# CP_State_LEDs.net
KiCad netlist of a schematic drawn in EAGLE
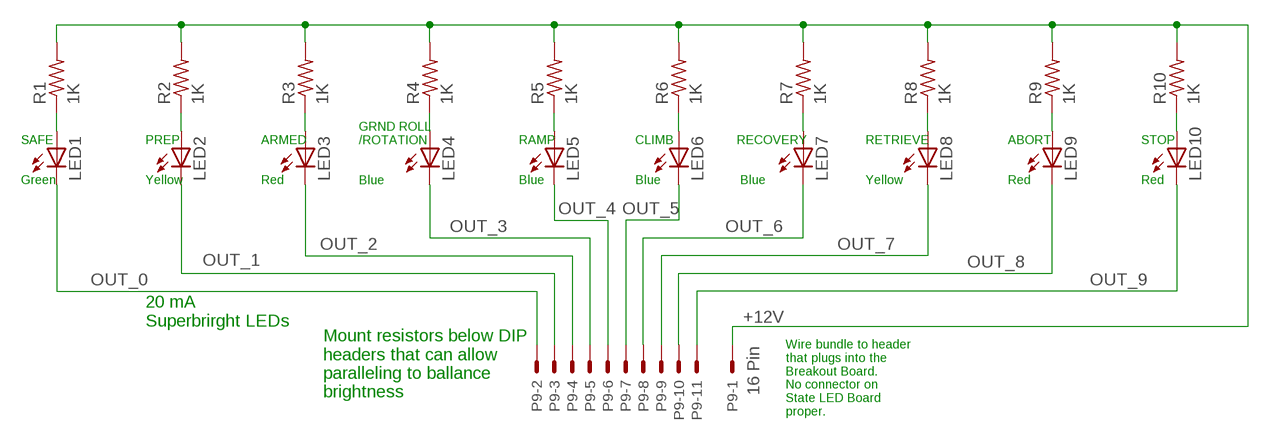
[diagram p0: schematic, sheet 1]

(export (version "E")
  (design (tool "Eeschema 10.0.6"))
  (components
    (comp (ref "LED1")
      (value "LED5MM")
      (footprint "eagle-import:LED5MM")
      (libsource (lib "eagle-import") (part "LED5MM"))
    )
    (comp (ref "LED2")
      (value "LED5MM")
      (footprint "eagle-import:LED5MM")
      (libsource (lib "eagle-import") (part "LED5MM"))
    )
    (comp (ref "LED3")
      (value "LED5MM")
      (footprint "eagle-import:LED5MM")
      (libsource (lib "eagle-import") (part "LED5MM"))
    )
    (comp (ref "LED4")
      (value "LED5MM")
      (footprint "eagle-import:LED5MM")
      (libsource (lib "eagle-import") (part "LED5MM"))
    )
    (comp (ref "LED5")
      (value "LED5MM")
      (footprint "eagle-import:LED5MM")
      (libsource (lib "eagle-import") (part "LED5MM"))
    )
    (comp (ref "LED6")
      (value "LED5MM")
      (footprint "eagle-import:LED5MM")
      (libsource (lib "eagle-import") (part "LED5MM"))
    )
    (comp (ref "LED7")
      (value "LED5MM")
      (footprint "eagle-import:LED5MM")
      (libsource (lib "eagle-import") (part "LED5MM"))
    )
    (comp (ref "LED8")
      (value "LED5MM")
      (footprint "eagle-import:LED5MM")
      (libsource (lib "eagle-import") (part "LED5MM"))
    )
    (comp (ref "LED9")
      (value "LED5MM")
      (footprint "eagle-import:LED5MM")
      (libsource (lib "eagle-import") (part "LED5MM"))
    )
    (comp (ref "LED10")
      (value "LED5MM")
      (footprint "eagle-import:LED5MM")
      (libsource (lib "eagle-import") (part "LED5MM"))
    )
    (comp (ref "P9")
      (value "16 Pin")
      (footprint "eagle-import:70543-20")
      (libsource (lib "eagle-import") (part "C-GRID-20-70543"))
    )
    (comp (ref "R1")
      (value "1K")
      (footprint "eagle-import:V234_12")
      (libsource (lib "eagle-import") (part "R-US_V234/12"))
    )
    (comp (ref "R2")
      (value "1K")
      (footprint "eagle-import:V234_12")
      (libsource (lib "eagle-import") (part "R-US_V234/12"))
    )
    (comp (ref "R3")
      (value "1K")
      (footprint "eagle-import:V234_12")
      (libsource (lib "eagle-import") (part "R-US_V234/12"))
    )
    (comp (ref "R4")
      (value "1K")
      (footprint "eagle-import:V234_12")
      (libsource (lib "eagle-import") (part "R-US_V234/12"))
    )
    (comp (ref "R5")
      (value "1K")
      (footprint "eagle-import:V234_12")
      (libsource (lib "eagle-import") (part "R-US_V234/12"))
    )
    (comp (ref "R6")
      (value "1K")
      (footprint "eagle-import:V234_12")
      (libsource (lib "eagle-import") (part "R-US_V234/12"))
    )
    (comp (ref "R7")
      (value "1K")
      (footprint "eagle-import:V234_12")
      (libsource (lib "eagle-import") (part "R-US_V234/12"))
    )
    (comp (ref "R8")
      (value "1K")
      (footprint "eagle-import:V234_12")
      (libsource (lib "eagle-import") (part "R-US_V234/12"))
    )
    (comp (ref "R9")
      (value "1K")
      (footprint "eagle-import:V234_12")
      (libsource (lib "eagle-import") (part "R-US_V234/12"))
    )
    (comp (ref "R10")
      (value "1K")
      (footprint "eagle-import:V234_12")
      (libsource (lib "eagle-import") (part "R-US_V234/12"))
    )
  )
  (nets
    (net (code "1") (name "/+12V") (class "Default")
      (node (ref "P9") (pin "1") (pinfunction "S_1") (pintype "passive"))
      (node (ref "R1") (pin "2") (pinfunction "2_2") (pintype "passive"))
      (node (ref "R10") (pin "2") (pinfunction "2_2") (pintype "passive"))
      (node (ref "R2") (pin "2") (pinfunction "2_2") (pintype "passive"))
      (node (ref "R3") (pin "2") (pinfunction "2_2") (pintype "passive"))
      (node (ref "R4") (pin "2") (pinfunction "2_2") (pintype "passive"))
      (node (ref "R5") (pin "2") (pinfunction "2_2") (pintype "passive"))
      (node (ref "R6") (pin "2") (pinfunction "2_2") (pintype "passive"))
      (node (ref "R7") (pin "2") (pinfunction "2_2") (pintype "passive"))
      (node (ref "R8") (pin "2") (pinfunction "2_2") (pintype "passive"))
      (node (ref "R9") (pin "2") (pinfunction "2_2") (pintype "passive"))
    )
    (net (code "2") (name "/OUT_0") (class "Default")
      (node (ref "LED1") (pin "K") (pinfunction "C_K") (pintype "passive"))
      (node (ref "P9") (pin "2") (pinfunction "S_2") (pintype "passive"))
    )
    (net (code "3") (name "/OUT_1") (class "Default")
      (node (ref "LED2") (pin "K") (pinfunction "C_K") (pintype "passive"))
      (node (ref "P9") (pin "3") (pinfunction "S_3") (pintype "passive"))
    )
    (net (code "4") (name "/OUT_2") (class "Default")
      (node (ref "LED3") (pin "K") (pinfunction "C_K") (pintype "passive"))
      (node (ref "P9") (pin "4") (pinfunction "S_4") (pintype "passive"))
    )
    (net (code "5") (name "/OUT_3") (class "Default")
      (node (ref "LED4") (pin "K") (pinfunction "C_K") (pintype "passive"))
      (node (ref "P9") (pin "5") (pinfunction "S_5") (pintype "passive"))
    )
    (net (code "6") (name "/OUT_4") (class "Default")
      (node (ref "LED5") (pin "K") (pinfunction "C_K") (pintype "passive"))
      (node (ref "P9") (pin "6") (pinfunction "S_6") (pintype "passive"))
    )
    (net (code "7") (name "/OUT_5") (class "Default")
      (node (ref "LED6") (pin "K") (pinfunction "C_K") (pintype "passive"))
      (node (ref "P9") (pin "7") (pinfunction "S_7") (pintype "passive"))
    )
    (net (code "8") (name "/OUT_6") (class "Default")
      (node (ref "LED7") (pin "K") (pinfunction "C_K") (pintype "passive"))
      (node (ref "P9") (pin "8") (pinfunction "S_8") (pintype "passive"))
    )
    (net (code "9") (name "/OUT_7") (class "Default")
      (node (ref "LED8") (pin "K") (pinfunction "C_K") (pintype "passive"))
      (node (ref "P9") (pin "9") (pinfunction "S_9") (pintype "passive"))
    )
    (net (code "10") (name "/OUT_8") (class "Default")
      (node (ref "LED9") (pin "K") (pinfunction "C_K") (pintype "passive"))
      (node (ref "P9") (pin "10") (pinfunction "S_10") (pintype "passive"))
    )
    (net (code "11") (name "/OUT_9") (class "Default")
      (node (ref "LED10") (pin "K") (pinfunction "C_K") (pintype "passive"))
      (node (ref "P9") (pin "11") (pinfunction "S_11") (pintype "passive"))
    )
    (net (code "12") (name "Net-(LED1-PadA)") (class "Default")
      (node (ref "LED1") (pin "A") (pinfunction "A_A") (pintype "passive"))
      (node (ref "R1") (pin "1") (pinfunction "1_1") (pintype "passive"))
    )
    (net (code "13") (name "Net-(LED2-PadA)") (class "Default")
      (node (ref "LED2") (pin "A") (pinfunction "A_A") (pintype "passive"))
      (node (ref "R2") (pin "1") (pinfunction "1_1") (pintype "passive"))
    )
    (net (code "14") (name "Net-(LED3-PadA)") (class "Default")
      (node (ref "LED3") (pin "A") (pinfunction "A_A") (pintype "passive"))
      (node (ref "R3") (pin "1") (pinfunction "1_1") (pintype "passive"))
    )
    (net (code "15") (name "Net-(LED4-PadA)") (class "Default")
      (node (ref "LED4") (pin "A") (pinfunction "A_A") (pintype "passive"))
      (node (ref "R4") (pin "1") (pinfunction "1_1") (pintype "passive"))
    )
    (net (code "16") (name "Net-(LED5-PadA)") (class "Default")
      (node (ref "LED5") (pin "A") (pinfunction "A_A") (pintype "passive"))
      (node (ref "R5") (pin "1") (pinfunction "1_1") (pintype "passive"))
    )
    (net (code "17") (name "Net-(LED6-PadA)") (class "Default")
      (node (ref "LED6") (pin "A") (pinfunction "A_A") (pintype "passive"))
      (node (ref "R6") (pin "1") (pinfunction "1_1") (pintype "passive"))
    )
    (net (code "18") (name "Net-(LED7-PadA)") (class "Default")
      (node (ref "LED7") (pin "A") (pinfunction "A_A") (pintype "passive"))
      (node (ref "R7") (pin "1") (pinfunction "1_1") (pintype "passive"))
    )
    (net (code "19") (name "Net-(LED8-PadA)") (class "Default")
      (node (ref "LED8") (pin "A") (pinfunction "A_A") (pintype "passive"))
      (node (ref "R8") (pin "1") (pinfunction "1_1") (pintype "passive"))
    )
    (net (code "20") (name "Net-(LED9-PadA)") (class "Default")
      (node (ref "LED9") (pin "A") (pinfunction "A_A") (pintype "passive"))
      (node (ref "R9") (pin "1") (pinfunction "1_1") (pintype "passive"))
    )
    (net (code "21") (name "Net-(LED10-PadA)") (class "Default")
      (node (ref "LED10") (pin "A") (pinfunction "A_A") (pintype "passive"))
      (node (ref "R10") (pin "1") (pinfunction "1_1") (pintype "passive"))
    )
  )
)
